# ADC1.net
KiCad netlist of a schematic drawn in Altium Designer
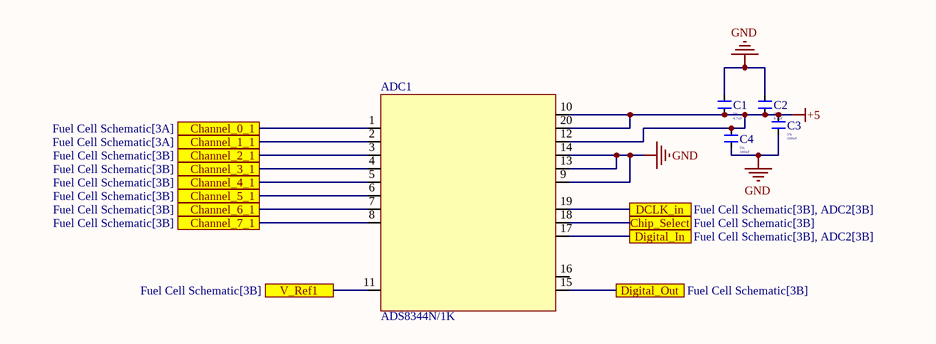
[diagram p0: ADC1.SchDoc]

(export (version "E")
  (design (tool "Eeschema 10.0.6"))
  (components
    (comp (ref "ADC1")
      (value "ADS8344N/1K")
      (footprint "ADS8344")
      (description "IC ADC 16BIT SAR 20SSOP")
      (fields (field (name "MANUFACTURER") "Texas Instruments"))
      (libsource (lib "Schlib1") (part "ADS8344N/1K"))
    )
    (comp (ref "C1")
      (value "~")
      (footprint "Capacitor_Kemet_0805")
      (description "CAP CER 4.7UF 16V X7R 0805")
      (fields
        (field (name "MANUFACTURER") "KEMET")
        (field (name "MANUFACTURER PART NUMBER") "C0805C475J4RACAUTO")
        (field (name "TOLERANCE") "5%")
        (field (name "CAPACITANCE") "4.7uF")
      )
      (libsource (lib "Schlib1") (part "C0805C475J4RACAUTO"))
    )
    (comp (ref "C2")
      (value "~")
      (footprint "Capacitor_Kemet_0805")
      (description "CAP CER 4.7UF 16V X7R 0805")
      (fields
        (field (name "MANUFACTURER") "KEMET")
        (field (name "MANUFACTURER PART NUMBER") "C0805C475J4RACAUTO")
        (field (name "TOLERANCE") "5%")
        (field (name "CAPACITANCE") "4.7uF")
      )
      (libsource (lib "Schlib1") (part "C0805C475J4RACAUTO"))
    )
    (comp (ref "C3")
      (value "~")
      (footprint "Capacitor_Kemet_0805")
      (description "Cap Ceramic 0.1uF 16V X7R 5% SMD 0805 125°C Plastic T/R")
      (fields
        (field (name "MANUFACTURER") "KEMET")
        (field (name "MANUFACTURER PART NUMBER") "C0805C104J4RACTU")
        (field (name "DISSIPATION FACTOR") "5%")
        (field (name "CAPACITANCE") "100nF")
      )
      (libsource (lib "Schlib1") (part "C0805C104J4RACTU"))
    )
    (comp (ref "C4")
      (value "~")
      (footprint "Capacitor_Kemet_0805")
      (description "Cap Ceramic 0.1uF 16V X7R 5% SMD 0805 125°C Plastic T/R")
      (fields
        (field (name "MANUFACTURER") "KEMET")
        (field (name "MANUFACTURER PART NUMBER") "C0805C104J4RACTU")
        (field (name "DISSIPATION FACTOR") "5%")
        (field (name "CAPACITANCE") "100nF")
      )
      (libsource (lib "Schlib1") (part "C0805C104J4RACTU"))
    )
  )
  (nets
    (net (code "1") (name "+5") (class "Default")
      (node (ref "ADC1") (pin "10") (pinfunction "Shutdown_10") (pintype "passive"))
      (node (ref "ADC1") (pin "12") (pinfunction "+VCC_12") (pintype "passive"))
      (node (ref "ADC1") (pin "20") (pinfunction "+VCC_20") (pintype "passive"))
      (node (ref "C1") (pin "1") (pinfunction "1_1") (pintype "passive"))
      (node (ref "C2") (pin "1") (pinfunction "1_1") (pintype "passive"))
      (node (ref "C3") (pin "2") (pinfunction "2_2") (pintype "passive"))
      (node (ref "C4") (pin "2") (pinfunction "2_2") (pintype "passive"))
    )
    (net (code "2") (name "/Channel_0_1") (class "Default")
      (node (ref "ADC1") (pin "1") (pinfunction "Channel_0_1") (pintype "passive"))
    )
    (net (code "3") (name "/Channel_1_1") (class "Default")
      (node (ref "ADC1") (pin "2") (pinfunction "Channel_1_2") (pintype "passive"))
    )
    (net (code "4") (name "/Channel_2_1") (class "Default")
      (node (ref "ADC1") (pin "3") (pinfunction "Channel_2_3") (pintype "passive"))
    )
    (net (code "5") (name "/Channel_3_1") (class "Default")
      (node (ref "ADC1") (pin "4") (pinfunction "Channel_3_4") (pintype "passive"))
    )
    (net (code "6") (name "/Channel_4_1") (class "Default")
      (node (ref "ADC1") (pin "5") (pinfunction "Channel_4_5") (pintype "passive"))
    )
    (net (code "7") (name "/Channel_5_1") (class "Default")
      (node (ref "ADC1") (pin "6") (pinfunction "Channel_5_6") (pintype "passive"))
    )
    (net (code "8") (name "/Channel_6_1") (class "Default")
      (node (ref "ADC1") (pin "7") (pinfunction "Channel_6_7") (pintype "passive"))
    )
    (net (code "9") (name "/Channel_7_1") (class "Default")
      (node (ref "ADC1") (pin "8") (pinfunction "Channel_7_8") (pintype "passive"))
    )
    (net (code "10") (name "/Chip_Select") (class "Default")
      (node (ref "ADC1") (pin "18") (pinfunction "Chip_Select_18") (pintype "passive"))
    )
    (net (code "11") (name "/DCLK_in") (class "Default")
      (node (ref "ADC1") (pin "19") (pinfunction "Digital_Clock_19") (pintype "passive"))
    )
    (net (code "12") (name "/Digital_In") (class "Default")
      (node (ref "ADC1") (pin "17") (pinfunction "Digital_In_17") (pintype "passive"))
    )
    (net (code "13") (name "/Digital_Out") (class "Default")
      (node (ref "ADC1") (pin "15") (pinfunction "Digital_Out_15") (pintype "passive"))
    )
    (net (code "14") (name "/V_Ref1") (class "Default")
      (node (ref "ADC1") (pin "11") (pinfunction "V_Reference_11") (pintype "passive"))
    )
    (net (code "15") (name "GND") (class "Default")
      (node (ref "ADC1") (pin "13") (pinfunction "Ground_13") (pintype "passive"))
      (node (ref "ADC1") (pin "14") (pinfunction "Ground_14") (pintype "passive"))
      (node (ref "ADC1") (pin "9") (pinfunction "Common_Reference_9") (pintype "passive"))
      (node (ref "C1") (pin "2") (pinfunction "2_2") (pintype "passive"))
      (node (ref "C2") (pin "2") (pinfunction "2_2") (pintype "passive"))
      (node (ref "C3") (pin "1") (pinfunction "1_1") (pintype "passive"))
      (node (ref "C4") (pin "1") (pinfunction "1_1") (pintype "passive"))
    )
    (net (code "16") (name "unconnected-(ADC1-Busy-Pad16)") (class "Default")
      (node (ref "ADC1") (pin "16") (pinfunction "Busy_16") (pintype "passive"))
    )
  )
)
